# rapidshark-lipo-sensor-mk-3_4.net
KiCad netlist of a schematic drawn in EAGLE
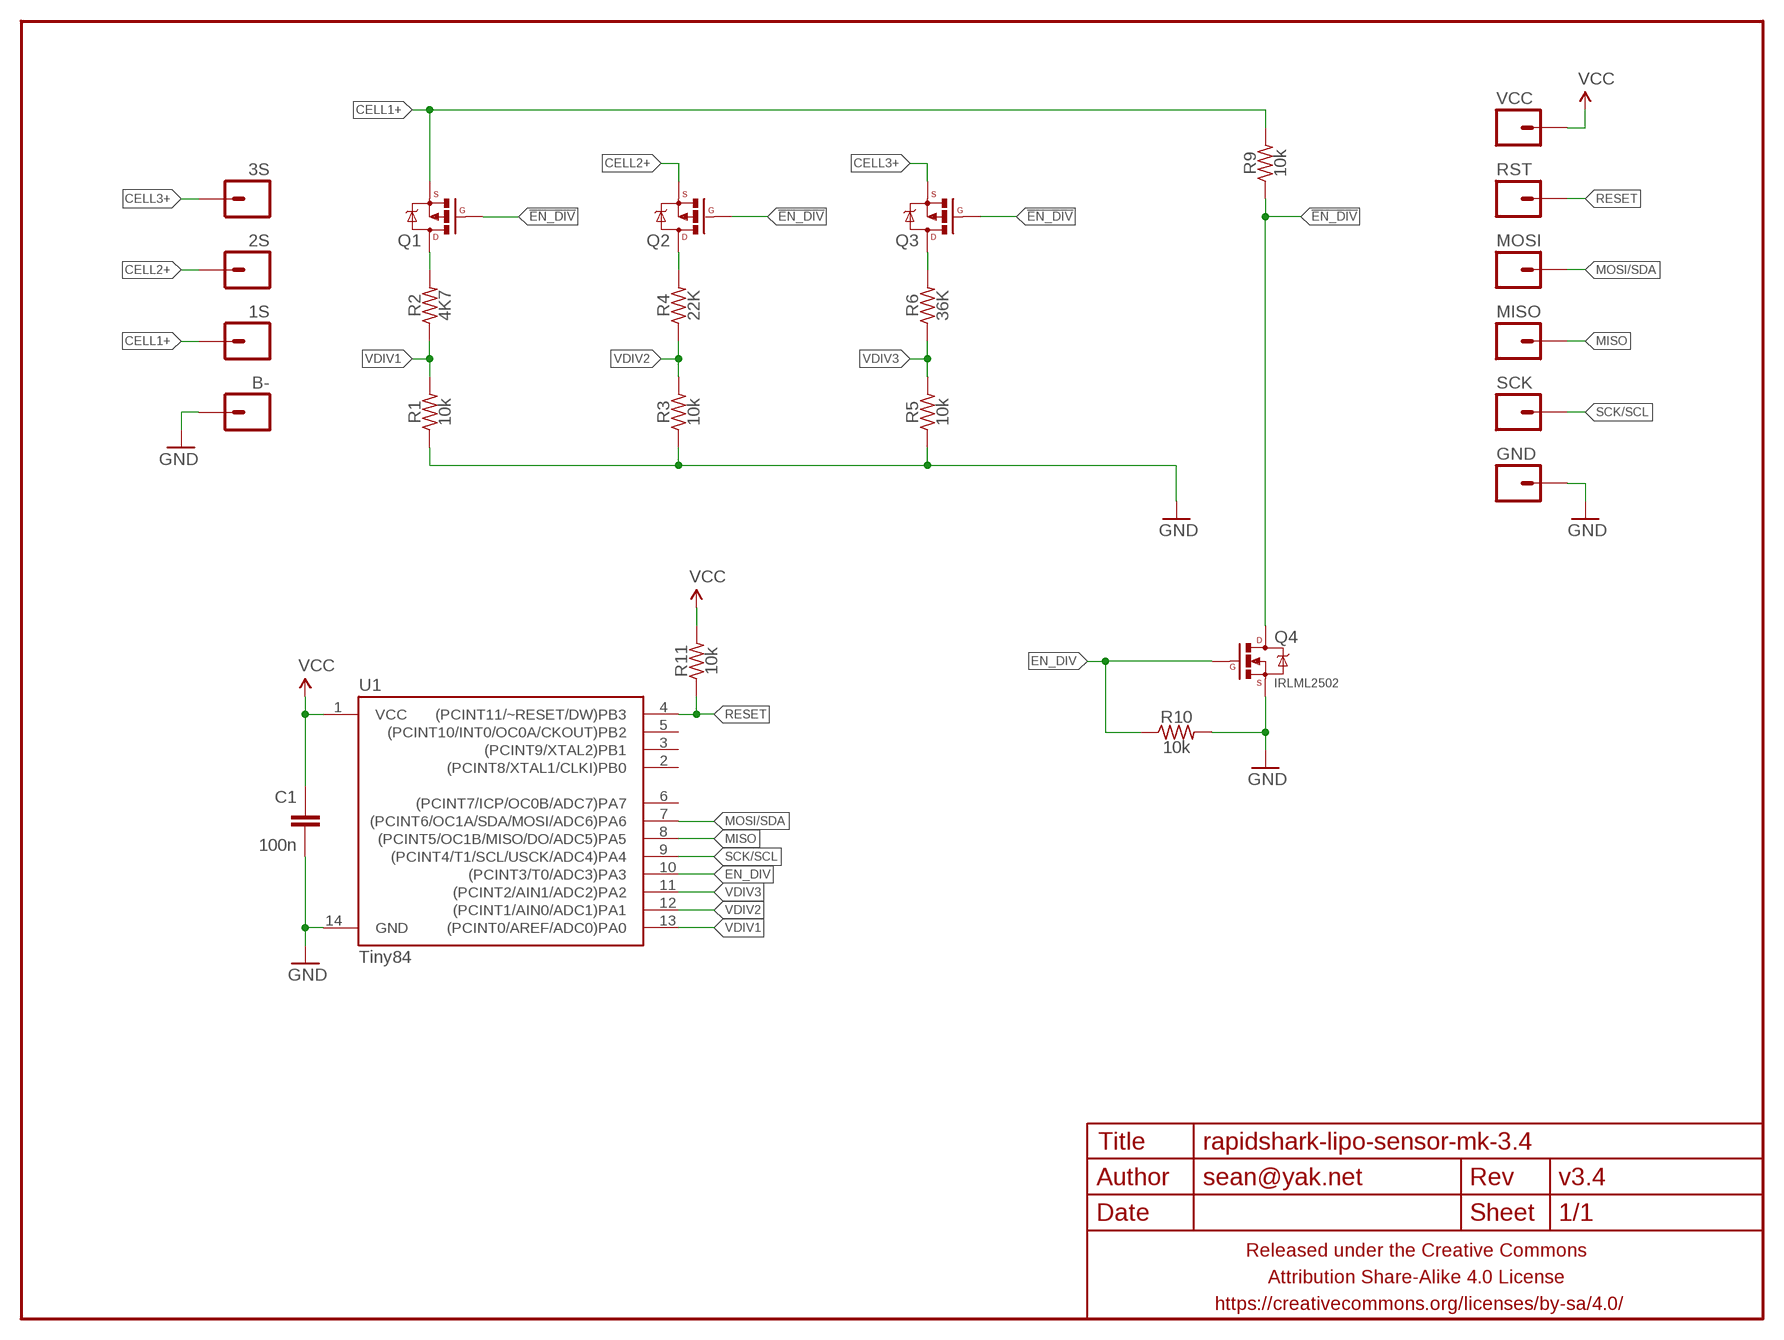
[diagram p0: schematic, sheet 1]

(export (version "E")
  (design (tool "Eeschema 10.0.6"))
  (components
    (comp (ref "1S")
      (value "M01PTH-0.9MM")
      (footprint "eagle-import:1X01-0.9MM")
      (libsource (lib "eagle-import") (part "M01PTH-0.9MM"))
    )
    (comp (ref "2S")
      (value "M01PTH-0.9MM")
      (footprint "eagle-import:1X01-0.9MM")
      (libsource (lib "eagle-import") (part "M01PTH-0.9MM"))
    )
    (comp (ref "3S")
      (value "M01PTH-0.9MM")
      (footprint "eagle-import:1X01-0.9MM")
      (libsource (lib "eagle-import") (part "M01PTH-0.9MM"))
    )
    (comp (ref "B-")
      (value "M01PTH-0.9MM")
      (footprint "eagle-import:1X01-0.9MM")
      (libsource (lib "eagle-import") (part "M01PTH-0.9MM"))
    )
    (comp (ref "C1")
      (value "100n")
      (footprint "eagle-import:C0603-TIGHTER")
      (libsource (lib "eagle-import") (part "CAPACITOR-CERAMICC0603-TIGHTER"))
    )
    (comp (ref "FRAME1")
      (value "FRAME-LETTERNO_PACKAGE")
      (footprint "eagle-import:DUMMY")
      (fields (field (name "DESIGNER") "sean@yak.net") (field (name "VERSION") "v3.4"))
      (libsource (lib "eagle-import") (part "FRAME-LETTERNO_PACKAGE"))
    )
    (comp (ref "GND")
      (value "M01PTH-0.9MM")
      (footprint "eagle-import:1X01-0.9MM")
      (libsource (lib "eagle-import") (part "M01PTH-0.9MM"))
    )
    (comp (ref "MISO")
      (value "M01PTH-0.9MM")
      (footprint "eagle-import:1X01-0.9MM")
      (libsource (lib "eagle-import") (part "M01PTH-0.9MM"))
    )
    (comp (ref "MOSI")
      (value "M01PTH-0.9MM")
      (footprint "eagle-import:1X01-0.9MM")
      (libsource (lib "eagle-import") (part "M01PTH-0.9MM"))
    )
    (comp (ref "Q1")
      (value "MOSFET-PCHANNELSOT-23")
      (footprint "eagle-import:SOT23")
      (libsource (lib "eagle-import") (part "MOSFET-PCHANNELSOT-23"))
    )
    (comp (ref "Q2")
      (value "MOSFET-PCHANNELSOT-23")
      (footprint "eagle-import:SOT23")
      (libsource (lib "eagle-import") (part "MOSFET-PCHANNELSOT-23"))
    )
    (comp (ref "Q3")
      (value "MOSFET-PCHANNELSOT-23")
      (footprint "eagle-import:SOT23")
      (libsource (lib "eagle-import") (part "MOSFET-PCHANNELSOT-23"))
    )
    (comp (ref "Q4")
      (value "IRLML2502")
      (footprint "eagle-import:SOT23")
      (libsource (lib "eagle-import") (part "MOSFET-NCHANNELIRLML2502"))
    )
    (comp (ref "R1")
      (value "10k")
      (footprint "eagle-import:R0603-TIGHTER")
      (libsource (lib "eagle-import") (part "RESISTORR0603-TIGHTER"))
    )
    (comp (ref "R2")
      (value "4K7")
      (footprint "eagle-import:R0603-TIGHTER")
      (libsource (lib "eagle-import") (part "RESISTORR0603-TIGHTER"))
    )
    (comp (ref "R3")
      (value "10k")
      (footprint "eagle-import:R0603-TIGHTER")
      (libsource (lib "eagle-import") (part "RESISTORR0603-TIGHTER"))
    )
    (comp (ref "R4")
      (value "22K")
      (footprint "eagle-import:R0603-TIGHTER")
      (libsource (lib "eagle-import") (part "RESISTORR0603-TIGHTER"))
    )
    (comp (ref "R5")
      (value "10k")
      (footprint "eagle-import:R0603-TIGHTER")
      (libsource (lib "eagle-import") (part "RESISTORR0603-TIGHTER"))
    )
    (comp (ref "R6")
      (value "36K")
      (footprint "eagle-import:R0603-TIGHTER")
      (libsource (lib "eagle-import") (part "RESISTORR0603-TIGHTER"))
    )
    (comp (ref "R9")
      (value "10k")
      (footprint "eagle-import:R0603-TIGHTER")
      (libsource (lib "eagle-import") (part "RESISTORR0603-TIGHTER"))
    )
    (comp (ref "R10")
      (value "10k")
      (footprint "eagle-import:R0603-TIGHTER")
      (libsource (lib "eagle-import") (part "RESISTORR0603-TIGHTER"))
    )
    (comp (ref "R11")
      (value "10k")
      (footprint "eagle-import:R0603-TIGHTER")
      (libsource (lib "eagle-import") (part "RESISTORR0603-TIGHTER"))
    )
    (comp (ref "RST")
      (value "M01PTH-0.9MM")
      (footprint "eagle-import:1X01-0.9MM")
      (libsource (lib "eagle-import") (part "M01PTH-0.9MM"))
    )
    (comp (ref "SCK")
      (value "M01PTH-0.9MM")
      (footprint "eagle-import:1X01-0.9MM")
      (libsource (lib "eagle-import") (part "M01PTH-0.9MM"))
    )
    (comp (ref "U1")
      (value "Tiny84")
      (footprint "eagle-import:SO14")
      (libsource (lib "eagle-import") (part "ATTINY84"))
    )
    (comp (ref "VCC")
      (value "M01PTH-0.9MM")
      (footprint "eagle-import:1X01-0.9MM")
      (libsource (lib "eagle-import") (part "M01PTH-0.9MM"))
    )
  )
  (nets
    (net (code "1") (name "/~{EN_DIV}") (class "Default")
      (node (ref "Q1") (pin "1") (pinfunction "G_1") (pintype "passive"))
      (node (ref "Q2") (pin "1") (pinfunction "G_1") (pintype "passive"))
      (node (ref "Q3") (pin "1") (pinfunction "G_1") (pintype "passive"))
      (node (ref "Q4") (pin "3") (pinfunction "D_3") (pintype "passive"))
      (node (ref "R9") (pin "1") (pinfunction "1_1") (pintype "passive"))
    )
    (net (code "2") (name "CELL1+") (class "Default")
      (node (ref "1S") (pin "1") (pinfunction "1_1") (pintype "passive"))
      (node (ref "Q1") (pin "2") (pinfunction "S_2") (pintype "passive"))
      (node (ref "R9") (pin "2") (pinfunction "2_2") (pintype "passive"))
    )
    (net (code "3") (name "CELL2+") (class "Default")
      (node (ref "2S") (pin "1") (pinfunction "1_1") (pintype "passive"))
      (node (ref "Q2") (pin "2") (pinfunction "S_2") (pintype "passive"))
    )
    (net (code "4") (name "CELL3+") (class "Default")
      (node (ref "3S") (pin "1") (pinfunction "1_1") (pintype "passive"))
      (node (ref "Q3") (pin "2") (pinfunction "S_2") (pintype "passive"))
    )
    (net (code "5") (name "EN_DIV") (class "Default")
      (node (ref "Q4") (pin "1") (pinfunction "G_1") (pintype "passive"))
      (node (ref "R10") (pin "1") (pinfunction "1_1") (pintype "passive"))
      (node (ref "U1") (pin "10") (pinfunction "(PCINT3/T0/ADC3)PA3_10") (pintype "bidirectional"))
    )
    (net (code "6") (name "GND") (class "Default")
      (node (ref "B-") (pin "1") (pinfunction "1_1") (pintype "passive"))
      (node (ref "C1") (pin "2") (pinfunction "2_2") (pintype "passive"))
      (node (ref "GND") (pin "1") (pinfunction "1_1") (pintype "passive"))
      (node (ref "Q4") (pin "2") (pinfunction "S_2") (pintype "passive"))
      (node (ref "R1") (pin "1") (pinfunction "1_1") (pintype "passive"))
      (node (ref "R10") (pin "2") (pinfunction "2_2") (pintype "passive"))
      (node (ref "R3") (pin "1") (pinfunction "1_1") (pintype "passive"))
      (node (ref "R5") (pin "1") (pinfunction "1_1") (pintype "passive"))
      (node (ref "U1") (pin "14") (pinfunction "GND_14") (pintype "bidirectional"))
    )
    (net (code "7") (name "MISO") (class "Default")
      (node (ref "MISO") (pin "1") (pinfunction "1_1") (pintype "passive"))
      (node (ref "U1") (pin "8") (pinfunction "(PCINT5/OC1B/MISO/DO/ADC5)PA5_8") (pintype "bidirectional"))
    )
    (net (code "8") (name "MOSI{slash}SDA") (class "Default")
      (node (ref "MOSI") (pin "1") (pinfunction "1_1") (pintype "passive"))
      (node (ref "U1") (pin "7") (pinfunction "(PCINT6/OC1A/SDA/MOSI/ADC6)PA6_7") (pintype "bidirectional"))
    )
    (net (code "9") (name "Net-(Q1-D)") (class "Default")
      (node (ref "Q1") (pin "3") (pinfunction "D_3") (pintype "passive"))
      (node (ref "R2") (pin "2") (pinfunction "2_2") (pintype "passive"))
    )
    (net (code "10") (name "Net-(Q2-D)") (class "Default")
      (node (ref "Q2") (pin "3") (pinfunction "D_3") (pintype "passive"))
      (node (ref "R4") (pin "2") (pinfunction "2_2") (pintype "passive"))
    )
    (net (code "11") (name "Net-(Q3-D)") (class "Default")
      (node (ref "Q3") (pin "3") (pinfunction "D_3") (pintype "passive"))
      (node (ref "R6") (pin "2") (pinfunction "2_2") (pintype "passive"))
    )
    (net (code "12") (name "RESET") (class "Default")
      (node (ref "R11") (pin "1") (pinfunction "1_1") (pintype "passive"))
      (node (ref "RST") (pin "1") (pinfunction "1_1") (pintype "passive"))
      (node (ref "U1") (pin "4") (pinfunction "(PCINT11/~{RESET/DW})PB3_4") (pintype "bidirectional"))
    )
    (net (code "13") (name "SCK{slash}SCL") (class "Default")
      (node (ref "SCK") (pin "1") (pinfunction "1_1") (pintype "passive"))
      (node (ref "U1") (pin "9") (pinfunction "(PCINT4/T1/SCL/USCK/ADC4)PA4_9") (pintype "bidirectional"))
    )
    (net (code "14") (name "VCC") (class "Default")
      (node (ref "C1") (pin "1") (pinfunction "1_1") (pintype "passive"))
      (node (ref "R11") (pin "2") (pinfunction "2_2") (pintype "passive"))
      (node (ref "U1") (pin "1") (pinfunction "VCC_1") (pintype "bidirectional"))
      (node (ref "VCC") (pin "1") (pinfunction "1_1") (pintype "passive"))
    )
    (net (code "15") (name "VDIV1") (class "Default")
      (node (ref "R1") (pin "2") (pinfunction "2_2") (pintype "passive"))
      (node (ref "R2") (pin "1") (pinfunction "1_1") (pintype "passive"))
      (node (ref "U1") (pin "13") (pinfunction "(PCINT0/AREF/ADC0)PA0_13") (pintype "bidirectional"))
    )
    (net (code "16") (name "VDIV2") (class "Default")
      (node (ref "R3") (pin "2") (pinfunction "2_2") (pintype "passive"))
      (node (ref "R4") (pin "1") (pinfunction "1_1") (pintype "passive"))
      (node (ref "U1") (pin "12") (pinfunction "(PCINT1/AIN0/ADC1)PA1_12") (pintype "bidirectional"))
    )
    (net (code "17") (name "VDIV3") (class "Default")
      (node (ref "R5") (pin "2") (pinfunction "2_2") (pintype "passive"))
      (node (ref "R6") (pin "1") (pinfunction "1_1") (pintype "passive"))
      (node (ref "U1") (pin "11") (pinfunction "(PCINT2/AIN1/ADC2)PA2_11") (pintype "bidirectional"))
    )
    (net (code "18") (name "unconnected-(U1-(PCINT7{slash}ICP{slash}OC0B{slash}ADC7)PA7-Pad6)") (class "Default")
      (node (ref "U1") (pin "6") (pinfunction "(PCINT7/ICP/OC0B/ADC7)PA7_6") (pintype "bidirectional"))
    )
    (net (code "19") (name "unconnected-(U1-(PCINT8{slash}XTAL1{slash}CLKI)PB0-Pad2)") (class "Default")
      (node (ref "U1") (pin "2") (pinfunction "(PCINT8/XTAL1/CLKI)PB0_2") (pintype "bidirectional"))
    )
    (net (code "20") (name "unconnected-(U1-(PCINT9{slash}XTAL2)PB1-Pad3)") (class "Default")
      (node (ref "U1") (pin "3") (pinfunction "(PCINT9/XTAL2)PB1_3") (pintype "bidirectional"))
    )
    (net (code "21") (name "unconnected-(U1-(PCINT10{slash}INT0{slash}OC0A{slash}CKOUT)PB2-Pad5)") (class "Default")
      (node (ref "U1") (pin "5") (pinfunction "(PCINT10/INT0/OC0A/CKOUT)PB2_5") (pintype "bidirectional"))
    )
  )
)
